# PWM_OUTS.net
KiCad netlist of a schematic drawn in Altium Designer
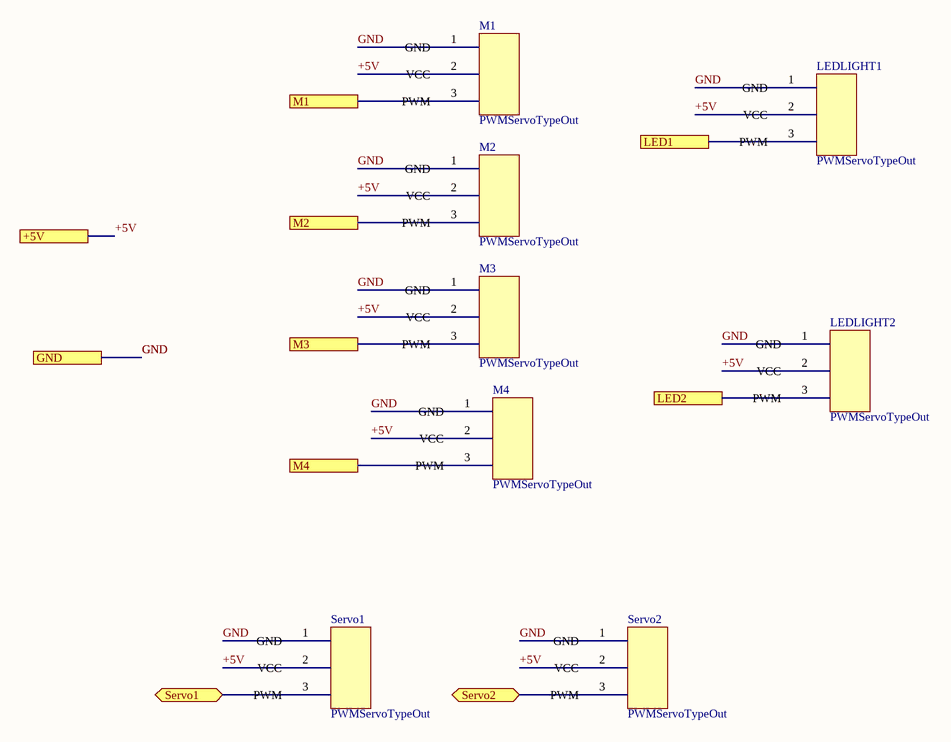
[diagram p0: PWM_OUTS.SchDoc]

(export (version "E")
  (design (tool "Eeschema 10.0.6"))
  (components
    (comp (ref "LEDLIGHT1")
      (value "PWMServoTypeOut")
      (footprint "HDR1X3")
      (libsource (lib "XSUB_COMP") (part "PWMServoTypeOut"))
    )
    (comp (ref "LEDLIGHT2")
      (value "PWMServoTypeOut")
      (footprint "HDR1X3")
      (libsource (lib "XSUB_COMP") (part "PWMServoTypeOut"))
    )
    (comp (ref "M1")
      (value "PWMServoTypeOut")
      (footprint "HDR1X3")
      (libsource (lib "XSUB_COMP") (part "PWMServoTypeOut"))
    )
    (comp (ref "M2")
      (value "PWMServoTypeOut")
      (footprint "HDR1X3")
      (libsource (lib "XSUB_COMP") (part "PWMServoTypeOut"))
    )
    (comp (ref "M3")
      (value "PWMServoTypeOut")
      (footprint "HDR1X3")
      (libsource (lib "XSUB_COMP") (part "PWMServoTypeOut"))
    )
    (comp (ref "M4")
      (value "PWMServoTypeOut")
      (footprint "HDR1X3")
      (libsource (lib "XSUB_COMP") (part "PWMServoTypeOut"))
    )
    (comp (ref "Servo1")
      (value "PWMServoTypeOut")
      (footprint "HDR1X3")
      (libsource (lib "XSUB_COMP") (part "PWMServoTypeOut"))
    )
    (comp (ref "Servo2")
      (value "PWMServoTypeOut")
      (footprint "HDR1X3")
      (libsource (lib "XSUB_COMP") (part "PWMServoTypeOut"))
    )
  )
  (nets
    (net (code "1") (name "/+5V") (class "Default")
      (node (ref "LEDLIGHT1") (pin "2") (pinfunction "VCC_2") (pintype "power_in"))
      (node (ref "LEDLIGHT2") (pin "2") (pinfunction "VCC_2") (pintype "power_in"))
      (node (ref "M1") (pin "2") (pinfunction "VCC_2") (pintype "power_in"))
      (node (ref "M2") (pin "2") (pinfunction "VCC_2") (pintype "power_in"))
      (node (ref "M3") (pin "2") (pinfunction "VCC_2") (pintype "power_in"))
      (node (ref "M4") (pin "2") (pinfunction "VCC_2") (pintype "power_in"))
      (node (ref "Servo1") (pin "2") (pinfunction "VCC_2") (pintype "power_in"))
      (node (ref "Servo2") (pin "2") (pinfunction "VCC_2") (pintype "power_in"))
    )
    (net (code "2") (name "/GND") (class "Default")
      (node (ref "LEDLIGHT1") (pin "1") (pinfunction "GND_1") (pintype "power_in"))
      (node (ref "LEDLIGHT2") (pin "1") (pinfunction "GND_1") (pintype "power_in"))
      (node (ref "M1") (pin "1") (pinfunction "GND_1") (pintype "power_in"))
      (node (ref "M2") (pin "1") (pinfunction "GND_1") (pintype "power_in"))
      (node (ref "M3") (pin "1") (pinfunction "GND_1") (pintype "power_in"))
      (node (ref "M4") (pin "1") (pinfunction "GND_1") (pintype "power_in"))
      (node (ref "Servo1") (pin "1") (pinfunction "GND_1") (pintype "power_in"))
      (node (ref "Servo2") (pin "1") (pinfunction "GND_1") (pintype "power_in"))
    )
    (net (code "3") (name "/LED1") (class "Default")
      (node (ref "LEDLIGHT1") (pin "3") (pinfunction "PWM_3") (pintype "passive"))
    )
    (net (code "4") (name "/LED2") (class "Default")
      (node (ref "LEDLIGHT2") (pin "3") (pinfunction "PWM_3") (pintype "passive"))
    )
    (net (code "5") (name "/M1") (class "Default")
      (node (ref "M1") (pin "3") (pinfunction "PWM_3") (pintype "passive"))
    )
    (net (code "6") (name "/M2") (class "Default")
      (node (ref "M2") (pin "3") (pinfunction "PWM_3") (pintype "passive"))
    )
    (net (code "7") (name "/M3") (class "Default")
      (node (ref "M3") (pin "3") (pinfunction "PWM_3") (pintype "passive"))
    )
    (net (code "8") (name "/M4") (class "Default")
      (node (ref "M4") (pin "3") (pinfunction "PWM_3") (pintype "passive"))
    )
    (net (code "9") (name "/Servo1") (class "Default")
      (node (ref "Servo1") (pin "3") (pinfunction "PWM_3") (pintype "passive"))
    )
    (net (code "10") (name "/Servo2") (class "Default")
      (node (ref "Servo2") (pin "3") (pinfunction "PWM_3") (pintype "passive"))
    )
  )
)
